# 06_Memories.net
KiCad netlist of a schematic drawn in Altium Designer
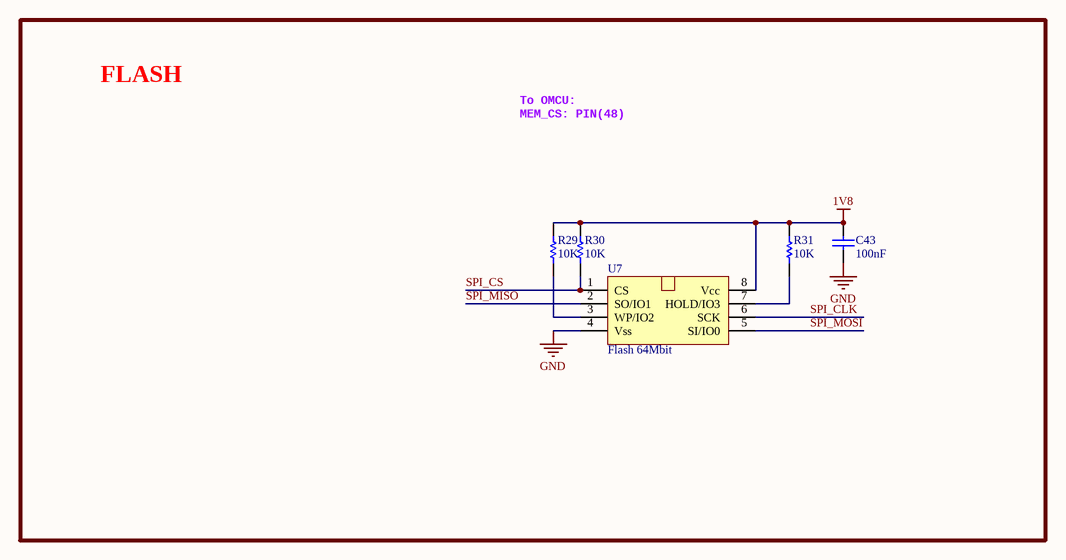
[diagram p0: 06 Memories.SchDoc]

(export (version "E")
  (design (tool "Eeschema 10.0.6"))
  (components
    (comp (ref "C43")
      (value "100nF")
      (footprint "0603 - C")
      (description "CAP CER 100nF 50V C0G/NP0 0603")
      (fields (field (name "VOLTAGE") "50V") (field (name "MPN") "CL10C104JB8NNNC"))
      (libsource (lib "Library_Chip") (part "Cap 0603 100nF"))
    )
    (comp (ref "R29")
      (value "10K")
      (footprint "0603 - R")
      (description "RES SMD 10K OHM 1% 1/10W 0603")
      (fields (field (name "MFR") "Yageo") (field (name "MPN") "RC0603FR-0710KL"))
      (libsource (lib "Library_Chip") (part "Res 0603 10K"))
    )
    (comp (ref "R30")
      (value "10K")
      (footprint "0603 - R")
      (description "RES SMD 10K OHM 1% 1/10W 0603")
      (fields (field (name "MFR") "Yageo") (field (name "MPN") "RC0603FR-0710KL"))
      (libsource (lib "Library_Chip") (part "Res 0603 10K"))
    )
    (comp (ref "R31")
      (value "10K")
      (footprint "0603 - R")
      (description "RES SMD 10K OHM 1% 1/10W 0603")
      (fields (field (name "MFR") "Yageo") (field (name "MPN") "RC0603FR-0710KL"))
      (libsource (lib "Library_Chip") (part "Res 0603 10K"))
    )
    (comp (ref "U7")
      (value "Flash 64Mbit")
      (footprint "8 - SOIC")
      (description "IC FLASH 64MBIT CMOS SPI 8SOIC")
      (fields (field (name "MFR") "Cypress") (field (name "MPN") "S25FL164K0XMFI013"))
      (libsource (lib "Library_IC") (part "Flash 64Mb SOIC8"))
    )
  )
  (nets
    (net (code "1") (name "/SPI_CLK") (class "Default")
      (node (ref "U7") (pin "6") (pinfunction "SCK_6") (pintype "passive"))
    )
    (net (code "2") (name "/SPI_CS") (class "Default")
      (node (ref "R30") (pin "1") (pinfunction "1_1") (pintype "passive"))
      (node (ref "U7") (pin "1") (pinfunction "CS_1") (pintype "passive"))
    )
    (net (code "3") (name "/SPI_MISO") (class "Default")
      (node (ref "U7") (pin "2") (pinfunction "SO/IO1_2") (pintype "passive"))
    )
    (net (code "4") (name "/SPI_MOSI") (class "Default")
      (node (ref "U7") (pin "5") (pinfunction "SI/IO0_5") (pintype "passive"))
    )
    (net (code "5") (name "1V8") (class "Default")
      (node (ref "C43") (pin "2") (pinfunction "2_2") (pintype "passive"))
      (node (ref "R29") (pin "2") (pinfunction "2_2") (pintype "passive"))
      (node (ref "R30") (pin "2") (pinfunction "2_2") (pintype "passive"))
      (node (ref "R31") (pin "2") (pinfunction "2_2") (pintype "passive"))
      (node (ref "U7") (pin "8") (pinfunction "Vcc_8") (pintype "passive"))
    )
    (net (code "6") (name "GND") (class "Default")
      (node (ref "C43") (pin "1") (pinfunction "1_1") (pintype "passive"))
      (node (ref "U7") (pin "4") (pinfunction "Vss_4") (pintype "passive"))
    )
    (net (code "7") (name "Net-(U7-HOLD{slash}IO3)") (class "Default")
      (node (ref "R31") (pin "1") (pinfunction "1_1") (pintype "passive"))
      (node (ref "U7") (pin "7") (pinfunction "HOLD/IO3_7") (pintype "passive"))
    )
    (net (code "8") (name "Net-(U7-WP{slash}IO2)") (class "Default")
      (node (ref "R29") (pin "1") (pinfunction "1_1") (pintype "passive"))
      (node (ref "U7") (pin "3") (pinfunction "WP/IO2_3") (pintype "passive"))
    )
  )
)
